# wife.net
KiCad netlist of a schematic drawn in EAGLE
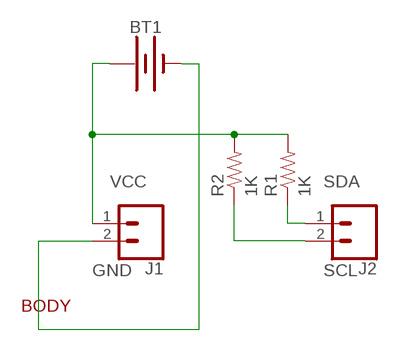
[diagram p0: schematic, sheet 1]

(export (version "E")
  (design (tool "Eeschema 10.0.6"))
  (components
    (comp (ref "BT1")
      (value "BATTERY-20MM_SMD")
      (footprint "eagle-import:BATTCON_20MM")
      (libsource (lib "eagle-import") (part "BATTERY-20MM_SMD"))
    )
    (comp (ref "J1")
      (value "CONN_02LOCK")
      (footprint "eagle-import:1X02_LOCK")
      (libsource (lib "eagle-import") (part "CONN_02LOCK"))
    )
    (comp (ref "J2")
      (value "CONN_02LOCK")
      (footprint "eagle-import:1X02_LOCK")
      (libsource (lib "eagle-import") (part "CONN_02LOCK"))
    )
    (comp (ref "R1")
      (value "1K")
      (footprint "eagle-import:AXIAL-0.3EZ")
      (libsource (lib "eagle-import") (part "1KOHM-1/4W-1%(PTH)HORIZ-KIT"))
    )
    (comp (ref "R2")
      (value "1K")
      (footprint "eagle-import:AXIAL-0.3EZ")
      (libsource (lib "eagle-import") (part "1KOHM-1/4W-1%(PTH)HORIZ-KIT"))
    )
    (comp (ref "U$1")
      (value "BODYWIFE")
      (footprint "eagle-import:WIFE")
      (libsource (lib "eagle-import") (part "BODYWIFE"))
    )
  )
  (nets
    (net (code "1") (name "/GND") (class "Default")
      (node (ref "BT1") (pin "2") (pinfunction "-_2") (pintype "power_in"))
      (node (ref "J1") (pin "2") (pinfunction "2_2") (pintype "passive"))
    )
    (net (code "2") (name "/SCL") (class "Default")
      (node (ref "J2") (pin "2") (pinfunction "2_2") (pintype "passive"))
      (node (ref "R2") (pin "P$1") (pinfunction "1_P$1") (pintype "passive"))
    )
    (net (code "3") (name "/SDA") (class "Default")
      (node (ref "J2") (pin "1") (pinfunction "1_1") (pintype "passive"))
      (node (ref "R1") (pin "P$1") (pinfunction "1_P$1") (pintype "passive"))
    )
    (net (code "4") (name "/VCC") (class "Default")
      (node (ref "BT1") (pin "1") (pinfunction "+_1") (pintype "power_in"))
      (node (ref "J1") (pin "1") (pinfunction "1_1") (pintype "passive"))
      (node (ref "R1") (pin "P$2") (pinfunction "2_P$2") (pintype "passive"))
      (node (ref "R2") (pin "P$2") (pinfunction "2_P$2") (pintype "passive"))
    )
  )
)
